# nano-master.net
KiCad netlist of a schematic drawn in EAGLE
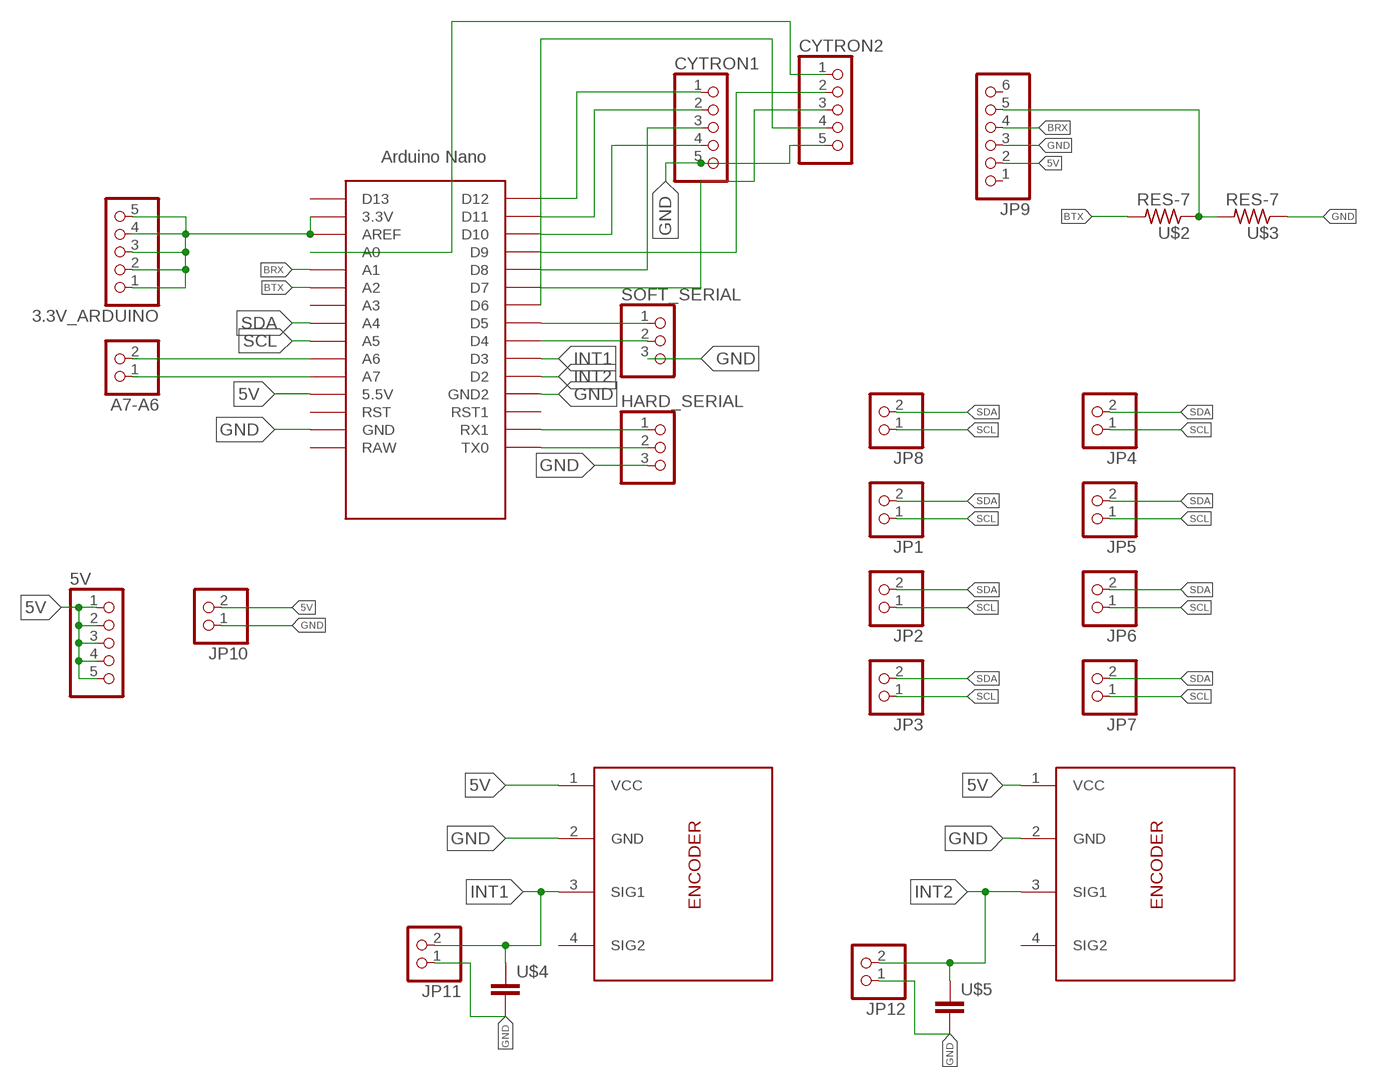
[diagram p0: schematic, sheet 1]

(export (version "E")
  (design (tool "Eeschema 10.0.6"))
  (components
    (comp (ref "3.3V_ARDUINO")
      (value "PINHD-1X5")
      (footprint "eagle-import:1X05")
      (libsource (lib "eagle-import") (part "pinhead_325_PINHD-1X5"))
    )
    (comp (ref "5V")
      (value "PINHD-1X5")
      (footprint "eagle-import:1X05")
      (libsource (lib "eagle-import") (part "PINHD-1X5"))
    )
    (comp (ref "A7-A6")
      (value "PINHD-1X2")
      (footprint "eagle-import:1X02")
      (libsource (lib "eagle-import") (part "PINHD-1X2"))
    )
    (comp (ref "CYTRON1")
      (value "PINHD-1X5")
      (footprint "eagle-import:1X05")
      (libsource (lib "eagle-import") (part "pinhead_325_PINHD-1X5"))
    )
    (comp (ref "CYTRON2")
      (value "PINHD-1X5")
      (footprint "eagle-import:1X05")
      (libsource (lib "eagle-import") (part "pinhead_325_PINHD-1X5"))
    )
    (comp (ref "ENCODER1")
      (value "ENCODER")
      (footprint "eagle-import:1X04")
      (libsource (lib "eagle-import") (part "ENCODER"))
    )
    (comp (ref "ENCODER2")
      (value "ENCODER")
      (footprint "eagle-import:1X04")
      (libsource (lib "eagle-import") (part "ENCODER"))
    )
    (comp (ref "HARD_SERIAL")
      (value "PINHD-1X3")
      (footprint "eagle-import:1X03")
      (libsource (lib "eagle-import") (part "PINHD-1X3"))
    )
    (comp (ref "JP1")
      (value "PINHD-2_DATA")
      (footprint "eagle-import:1X02")
      (libsource (lib "eagle-import") (part "PINHD-2_DATA"))
    )
    (comp (ref "JP2")
      (value "PINHD-2_DATA")
      (footprint "eagle-import:1X02")
      (libsource (lib "eagle-import") (part "PINHD-2_DATA"))
    )
    (comp (ref "JP3")
      (value "PINHD-2_DATA")
      (footprint "eagle-import:1X02")
      (libsource (lib "eagle-import") (part "PINHD-2_DATA"))
    )
    (comp (ref "JP4")
      (value "PINHD-2_DATA")
      (footprint "eagle-import:1X02")
      (libsource (lib "eagle-import") (part "PINHD-2_DATA"))
    )
    (comp (ref "JP5")
      (value "PINHD-2_DATA")
      (footprint "eagle-import:1X02")
      (libsource (lib "eagle-import") (part "PINHD-2_DATA"))
    )
    (comp (ref "JP6")
      (value "PINHD-2_DATA")
      (footprint "eagle-import:1X02")
      (libsource (lib "eagle-import") (part "PINHD-2_DATA"))
    )
    (comp (ref "JP7")
      (value "PINHD-2_DATA")
      (footprint "eagle-import:1X02")
      (libsource (lib "eagle-import") (part "PINHD-2_DATA"))
    )
    (comp (ref "JP8")
      (value "PINHD-2_DATA")
      (footprint "eagle-import:1X02")
      (libsource (lib "eagle-import") (part "PINHD-2_DATA"))
    )
    (comp (ref "JP9")
      (value "PINHD-1X6")
      (footprint "eagle-import:1X06")
      (libsource (lib "eagle-import") (part "PINHD-1X6"))
    )
    (comp (ref "JP10")
      (value "PINHD-2_DATA")
      (footprint "eagle-import:1X02")
      (libsource (lib "eagle-import") (part "PINHD-2_DATA"))
    )
    (comp (ref "JP11")
      (value "PINHD-2_DATA")
      (footprint "eagle-import:1X02")
      (libsource (lib "eagle-import") (part "PINHD-2_DATA"))
    )
    (comp (ref "JP12")
      (value "PINHD-2_DATA")
      (footprint "eagle-import:1X02")
      (libsource (lib "eagle-import") (part "PINHD-2_DATA"))
    )
    (comp (ref "SOFT_SERIAL")
      (value "PINHD-1X3")
      (footprint "eagle-import:1X03")
      (libsource (lib "eagle-import") (part "PINHD-1X3"))
    )
    (comp (ref "U$1")
      (value "NANO")
      (footprint "eagle-import:NANO")
      (libsource (lib "eagle-import") (part "NANO"))
    )
    (comp (ref "U$2")
      (value "RES-7")
      (footprint "eagle-import:0204_7")
      (libsource (lib "eagle-import") (part "RES-7"))
    )
    (comp (ref "U$3")
      (value "RES-7")
      (footprint "eagle-import:0204_7")
      (libsource (lib "eagle-import") (part "RES-7"))
    )
    (comp (ref "U$4")
      (value "CAPACITOR")
      (footprint "eagle-import:C025-025X050")
      (libsource (lib "eagle-import") (part "CAPACITOR"))
    )
    (comp (ref "U$5")
      (value "CAPACITOR")
      (footprint "eagle-import:C025-025X050")
      (libsource (lib "eagle-import") (part "CAPACITOR"))
    )
  )
  (nets
    (net (code "1") (name "5V") (class "Default")
      (node (ref "5V") (pin "1") (pinfunction "1_1") (pintype "passive"))
      (node (ref "5V") (pin "2") (pinfunction "2_2") (pintype "passive"))
      (node (ref "5V") (pin "3") (pinfunction "3_3") (pintype "passive"))
      (node (ref "5V") (pin "4") (pinfunction "4_4") (pintype "passive"))
      (node (ref "5V") (pin "5") (pinfunction "5_5") (pintype "passive"))
      (node (ref "ENCODER1") (pin "1") (pinfunction "VCC_1") (pintype "bidirectional"))
      (node (ref "ENCODER2") (pin "1") (pinfunction "VCC_1") (pintype "bidirectional"))
      (node (ref "JP10") (pin "2") (pinfunction "2_2") (pintype "passive"))
      (node (ref "JP9") (pin "2") (pinfunction "2_2") (pintype "passive"))
      (node (ref "U$1") (pin "5V") (pinfunction "5.5V_5V") (pintype "bidirectional"))
    )
    (net (code "2") (name "BRX") (class "Default")
      (node (ref "JP9") (pin "4") (pinfunction "4_4") (pintype "passive"))
      (node (ref "U$1") (pin "A1") (pinfunction "A1_A1") (pintype "bidirectional"))
    )
    (net (code "3") (name "BTX") (class "Default")
      (node (ref "U$1") (pin "A2") (pinfunction "A2_A2") (pintype "bidirectional"))
      (node (ref "U$2") (pin "2") (pinfunction "2_2") (pintype "passive"))
    )
    (net (code "4") (name "GND") (class "Default")
      (node (ref "CYTRON1") (pin "5") (pinfunction "5_5") (pintype "passive"))
      (node (ref "CYTRON2") (pin "5") (pinfunction "5_5") (pintype "passive"))
      (node (ref "ENCODER1") (pin "2") (pinfunction "GND_2") (pintype "bidirectional"))
      (node (ref "ENCODER2") (pin "2") (pinfunction "GND_2") (pintype "bidirectional"))
      (node (ref "HARD_SERIAL") (pin "3") (pinfunction "3_3") (pintype "passive"))
      (node (ref "JP10") (pin "1") (pinfunction "1_1") (pintype "passive"))
      (node (ref "JP11") (pin "1") (pinfunction "1_1") (pintype "passive"))
      (node (ref "JP12") (pin "1") (pinfunction "1_1") (pintype "passive"))
      (node (ref "JP9") (pin "3") (pinfunction "3_3") (pintype "passive"))
      (node (ref "SOFT_SERIAL") (pin "3") (pinfunction "3_3") (pintype "passive"))
      (node (ref "U$1") (pin "GND") (pinfunction "GND_GND") (pintype "bidirectional"))
      (node (ref "U$1") (pin "GND1") (pinfunction "GND2_GND1") (pintype "bidirectional"))
      (node (ref "U$3") (pin "1") (pinfunction "1_1") (pintype "passive"))
      (node (ref "U$4") (pin "2") (pinfunction "2_2") (pintype "passive"))
      (node (ref "U$5") (pin "2") (pinfunction "2_2") (pintype "passive"))
    )
    (net (code "5") (name "INT1") (class "Default")
      (node (ref "ENCODER2") (pin "3") (pinfunction "SIG1_3") (pintype "bidirectional"))
      (node (ref "JP11") (pin "2") (pinfunction "2_2") (pintype "passive"))
      (node (ref "U$1") (pin "D3") (pinfunction "D3_D3") (pintype "bidirectional"))
      (node (ref "U$4") (pin "1") (pinfunction "1_1") (pintype "passive"))
    )
    (net (code "6") (name "INT2") (class "Default")
      (node (ref "ENCODER1") (pin "3") (pinfunction "SIG1_3") (pintype "bidirectional"))
      (node (ref "JP12") (pin "2") (pinfunction "2_2") (pintype "passive"))
      (node (ref "U$1") (pin "D2") (pinfunction "D2_D2") (pintype "bidirectional"))
      (node (ref "U$5") (pin "1") (pinfunction "1_1") (pintype "passive"))
    )
    (net (code "7") (name "Net-(3.3V_ARDUINO-Pad1)") (class "Default")
      (node (ref "3.3V_ARDUINO") (pin "1") (pinfunction "1_1") (pintype "passive"))
      (node (ref "3.3V_ARDUINO") (pin "2") (pinfunction "2_2") (pintype "passive"))
      (node (ref "3.3V_ARDUINO") (pin "3") (pinfunction "3_3") (pintype "passive"))
      (node (ref "3.3V_ARDUINO") (pin "4") (pinfunction "4_4") (pintype "passive"))
      (node (ref "3.3V_ARDUINO") (pin "5") (pinfunction "5_5") (pintype "passive"))
      (node (ref "U$1") (pin "3.3V") (pinfunction "3.3V_3.3V") (pintype "bidirectional"))
      (node (ref "U$1") (pin "AREF") (pinfunction "AREF_AREF") (pintype "bidirectional"))
    )
    (net (code "8") (name "Net-(A7-A6-Pad1)") (class "Default")
      (node (ref "A7-A6") (pin "1") (pinfunction "1_1") (pintype "passive"))
      (node (ref "U$1") (pin "A7") (pinfunction "A7_A7") (pintype "bidirectional"))
    )
    (net (code "9") (name "Net-(A7-A6-Pad2)") (class "Default")
      (node (ref "A7-A6") (pin "2") (pinfunction "2_2") (pintype "passive"))
      (node (ref "U$1") (pin "A6") (pinfunction "A6_A6") (pintype "bidirectional"))
    )
    (net (code "10") (name "Net-(CYTRON1-Pad1)") (class "Default")
      (node (ref "CYTRON1") (pin "1") (pinfunction "1_1") (pintype "passive"))
      (node (ref "U$1") (pin "D12") (pinfunction "D12_D12") (pintype "bidirectional"))
    )
    (net (code "11") (name "Net-(CYTRON1-Pad2)") (class "Default")
      (node (ref "CYTRON1") (pin "2") (pinfunction "2_2") (pintype "passive"))
      (node (ref "U$1") (pin "D11") (pinfunction "D11_D11") (pintype "bidirectional"))
    )
    (net (code "12") (name "Net-(CYTRON1-Pad3)") (class "Default")
      (node (ref "CYTRON1") (pin "3") (pinfunction "3_3") (pintype "passive"))
      (node (ref "U$1") (pin "D8") (pinfunction "D8_D8") (pintype "bidirectional"))
    )
    (net (code "13") (name "Net-(CYTRON1-Pad4)") (class "Default")
      (node (ref "CYTRON1") (pin "4") (pinfunction "4_4") (pintype "passive"))
      (node (ref "U$1") (pin "D10") (pinfunction "D10_D10") (pintype "bidirectional"))
    )
    (net (code "14") (name "Net-(CYTRON2-Pad1)") (class "Default")
      (node (ref "CYTRON2") (pin "1") (pinfunction "1_1") (pintype "passive"))
      (node (ref "U$1") (pin "A0") (pinfunction "A0_A0") (pintype "bidirectional"))
    )
    (net (code "15") (name "Net-(CYTRON2-Pad2)") (class "Default")
      (node (ref "CYTRON2") (pin "2") (pinfunction "2_2") (pintype "passive"))
      (node (ref "U$1") (pin "D9") (pinfunction "D9_D9") (pintype "bidirectional"))
    )
    (net (code "16") (name "Net-(CYTRON2-Pad3)") (class "Default")
      (node (ref "CYTRON2") (pin "3") (pinfunction "3_3") (pintype "passive"))
      (node (ref "U$1") (pin "D7") (pinfunction "D7_D7") (pintype "bidirectional"))
    )
    (net (code "17") (name "Net-(CYTRON2-Pad4)") (class "Default")
      (node (ref "CYTRON2") (pin "4") (pinfunction "4_4") (pintype "passive"))
      (node (ref "U$1") (pin "D6") (pinfunction "D6_D6") (pintype "bidirectional"))
    )
    (net (code "18") (name "Net-(HARD_SERIAL-Pad1)") (class "Default")
      (node (ref "HARD_SERIAL") (pin "1") (pinfunction "1_1") (pintype "passive"))
      (node (ref "U$1") (pin "RX1") (pinfunction "RX1_RX1") (pintype "bidirectional"))
    )
    (net (code "19") (name "Net-(HARD_SERIAL-Pad2)") (class "Default")
      (node (ref "HARD_SERIAL") (pin "2") (pinfunction "2_2") (pintype "passive"))
      (node (ref "U$1") (pin "TX0") (pinfunction "TX0_TX0") (pintype "bidirectional"))
    )
    (net (code "20") (name "Net-(JP9-Pad5)") (class "Default")
      (node (ref "JP9") (pin "5") (pinfunction "5_5") (pintype "passive"))
      (node (ref "U$2") (pin "1") (pinfunction "1_1") (pintype "passive"))
      (node (ref "U$3") (pin "2") (pinfunction "2_2") (pintype "passive"))
    )
    (net (code "21") (name "Net-(SOFT_SERIAL-Pad1)") (class "Default")
      (node (ref "SOFT_SERIAL") (pin "1") (pinfunction "1_1") (pintype "passive"))
      (node (ref "U$1") (pin "D5") (pinfunction "D5_D5") (pintype "bidirectional"))
    )
    (net (code "22") (name "Net-(SOFT_SERIAL-Pad2)") (class "Default")
      (node (ref "SOFT_SERIAL") (pin "2") (pinfunction "2_2") (pintype "passive"))
      (node (ref "U$1") (pin "D4") (pinfunction "D4_D4") (pintype "bidirectional"))
    )
    (net (code "23") (name "SCL") (class "Default")
      (node (ref "JP1") (pin "1") (pinfunction "1_1") (pintype "passive"))
      (node (ref "JP2") (pin "1") (pinfunction "1_1") (pintype "passive"))
      (node (ref "JP3") (pin "1") (pinfunction "1_1") (pintype "passive"))
      (node (ref "JP4") (pin "1") (pinfunction "1_1") (pintype "passive"))
      (node (ref "JP5") (pin "1") (pinfunction "1_1") (pintype "passive"))
      (node (ref "JP6") (pin "1") (pinfunction "1_1") (pintype "passive"))
      (node (ref "JP7") (pin "1") (pinfunction "1_1") (pintype "passive"))
      (node (ref "JP8") (pin "1") (pinfunction "1_1") (pintype "passive"))
      (node (ref "U$1") (pin "A5") (pinfunction "A5_A5") (pintype "bidirectional"))
    )
    (net (code "24") (name "SDA") (class "Default")
      (node (ref "JP1") (pin "2") (pinfunction "2_2") (pintype "passive"))
      (node (ref "JP2") (pin "2") (pinfunction "2_2") (pintype "passive"))
      (node (ref "JP3") (pin "2") (pinfunction "2_2") (pintype "passive"))
      (node (ref "JP4") (pin "2") (pinfunction "2_2") (pintype "passive"))
      (node (ref "JP5") (pin "2") (pinfunction "2_2") (pintype "passive"))
      (node (ref "JP6") (pin "2") (pinfunction "2_2") (pintype "passive"))
      (node (ref "JP7") (pin "2") (pinfunction "2_2") (pintype "passive"))
      (node (ref "JP8") (pin "2") (pinfunction "2_2") (pintype "passive"))
      (node (ref "U$1") (pin "A4") (pinfunction "A4_A4") (pintype "bidirectional"))
    )
    (net (code "25") (name "unconnected-(ENCODER1-SIG2-Pad4)") (class "Default")
      (node (ref "ENCODER1") (pin "4") (pinfunction "SIG2_4") (pintype "bidirectional"))
    )
    (net (code "26") (name "unconnected-(ENCODER2-SIG2-Pad4)") (class "Default")
      (node (ref "ENCODER2") (pin "4") (pinfunction "SIG2_4") (pintype "bidirectional"))
    )
    (net (code "27") (name "unconnected-(JP9-Pad1)") (class "Default")
      (node (ref "JP9") (pin "1") (pinfunction "1_1") (pintype "passive"))
    )
    (net (code "28") (name "unconnected-(JP9-Pad6)") (class "Default")
      (node (ref "JP9") (pin "6") (pinfunction "6_6") (pintype "passive"))
    )
    (net (code "29") (name "unconnected-(U$1-PadA3)") (class "Default")
      (node (ref "U$1") (pin "A3") (pinfunction "A3_A3") (pintype "bidirectional"))
    )
    (net (code "30") (name "unconnected-(U$1-PadD13)") (class "Default")
      (node (ref "U$1") (pin "D13") (pinfunction "D13_D13") (pintype "bidirectional"))
    )
    (net (code "31") (name "unconnected-(U$1-PadRAW)") (class "Default")
      (node (ref "U$1") (pin "RAW") (pinfunction "RAW_RAW") (pintype "bidirectional"))
    )
    (net (code "32") (name "unconnected-(U$1-PadRST)") (class "Default")
      (node (ref "U$1") (pin "RST") (pinfunction "RST_RST") (pintype "bidirectional"))
    )
    (net (code "33") (name "unconnected-(U$1-PadRST1)") (class "Default")
      (node (ref "U$1") (pin "RST1") (pinfunction "RST1_RST1") (pintype "bidirectional"))
    )
  )
)
